# IOPROTO96.net
KiCad netlist of a schematic drawn in EAGLE
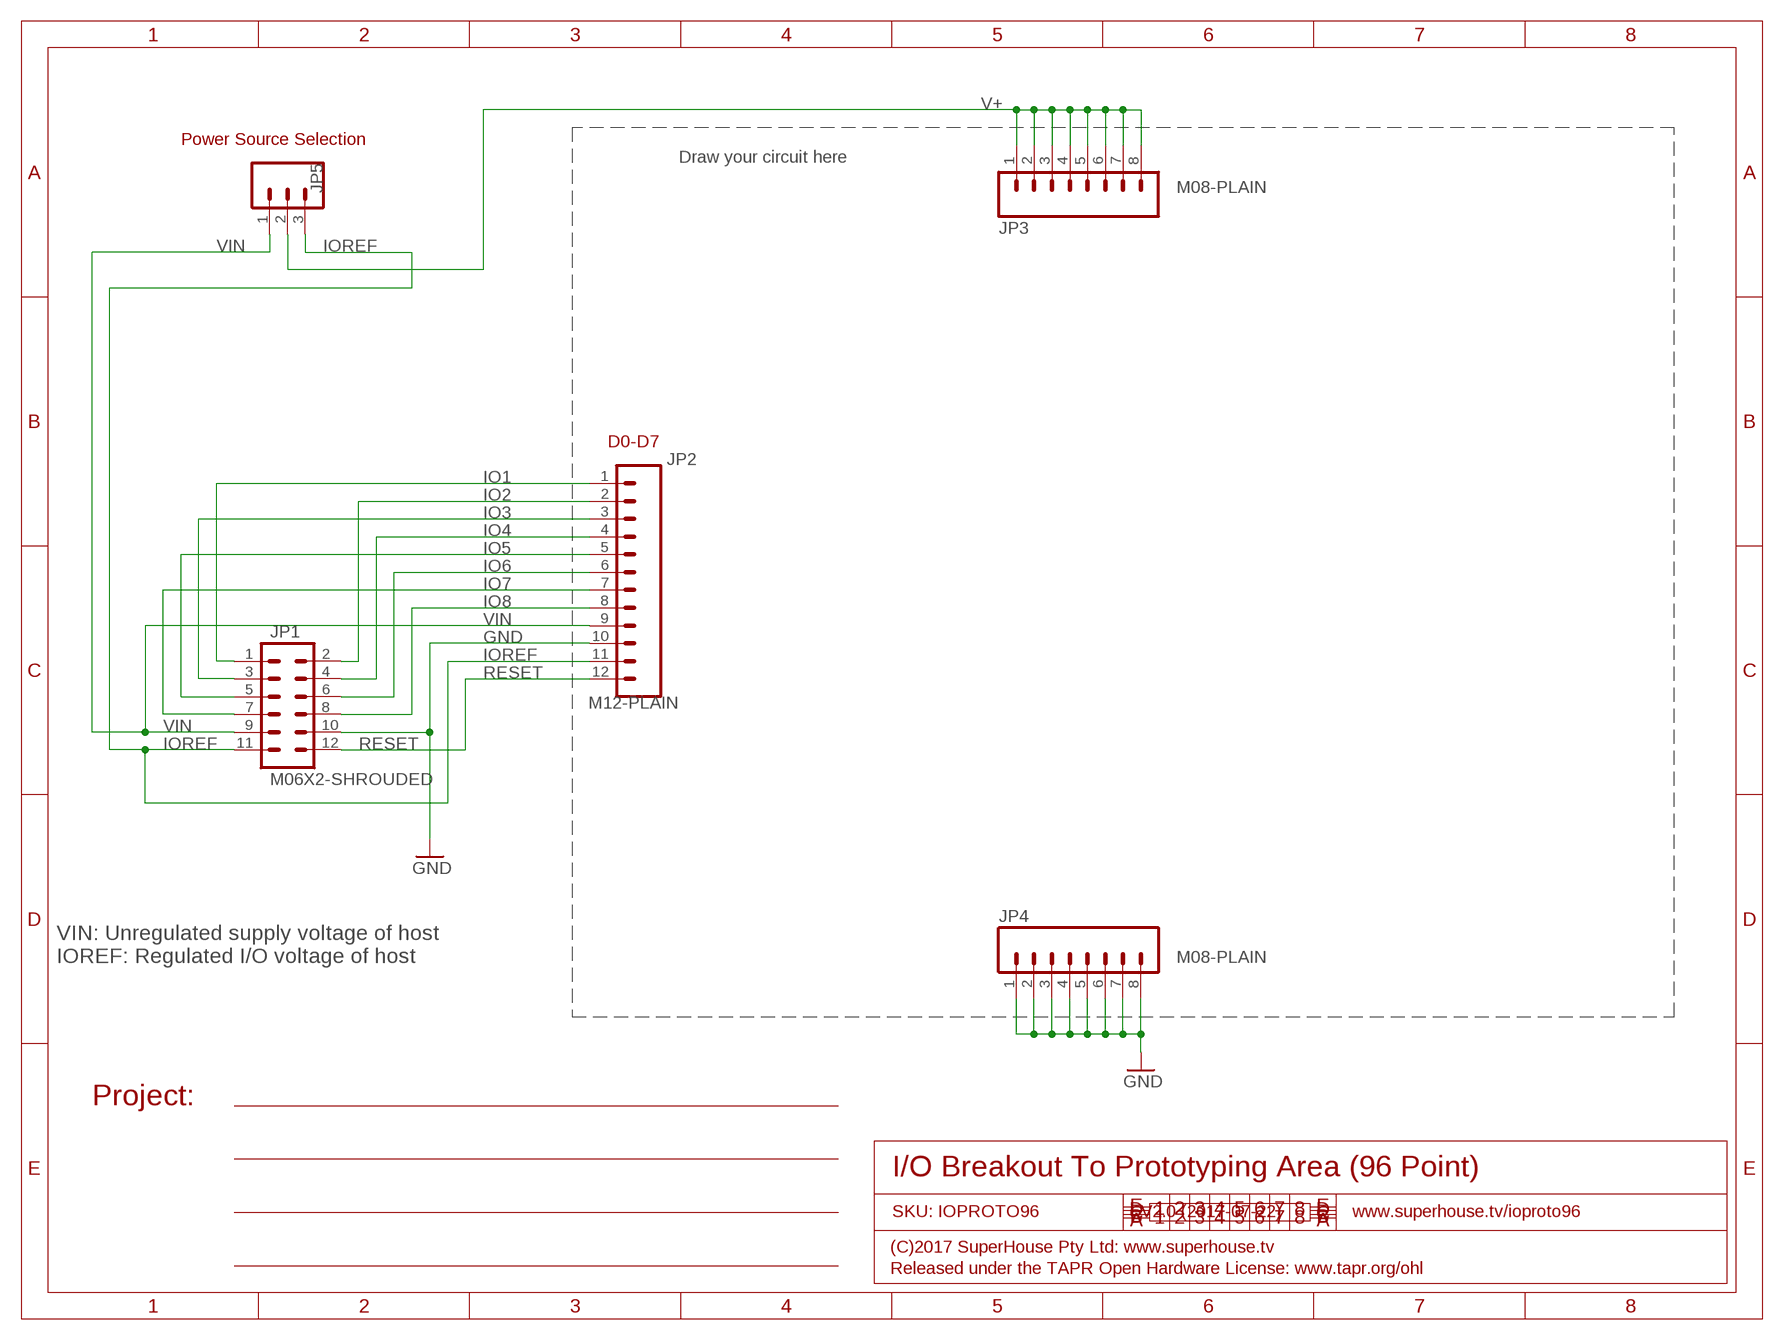
[diagram p0: schematic, sheet 1]

(export (version "E")
  (design (tool "Eeschema 10.0.6"))
  (components
    (comp (ref "JP1")
      (value "M06X2-SHROUDED")
      (footprint "eagle-import:2X6-SHROUDED")
      (libsource (lib "eagle-import") (part "M06X2-SHROUDED"))
    )
    (comp (ref "JP2")
      (value "M12-PLAIN")
      (footprint "eagle-import:1X12")
      (libsource (lib "eagle-import") (part "M12-PLAIN"))
    )
    (comp (ref "JP3")
      (value "M08-PLAIN")
      (footprint "eagle-import:1X08")
      (libsource (lib "eagle-import") (part "M08-PLAIN"))
    )
    (comp (ref "JP4")
      (value "M08-PLAIN")
      (footprint "eagle-import:1X08")
      (libsource (lib "eagle-import") (part "M08-PLAIN"))
    )
    (comp (ref "JP5")
      (value "M03-PIN")
      (footprint "eagle-import:1X03-P")
      (libsource (lib "eagle-import") (part "M03-PIN"))
    )
  )
  (nets
    (net (code "1") (name "/IO1") (class "Default")
      (node (ref "JP1") (pin "1") (pinfunction "1_1") (pintype "passive"))
      (node (ref "JP2") (pin "1") (pinfunction "1_1") (pintype "passive"))
    )
    (net (code "2") (name "/IO2") (class "Default")
      (node (ref "JP1") (pin "2") (pinfunction "2_2") (pintype "passive"))
      (node (ref "JP2") (pin "2") (pinfunction "2_2") (pintype "passive"))
    )
    (net (code "3") (name "/IO3") (class "Default")
      (node (ref "JP1") (pin "3") (pinfunction "3_3") (pintype "passive"))
      (node (ref "JP2") (pin "3") (pinfunction "3_3") (pintype "passive"))
    )
    (net (code "4") (name "/IO4") (class "Default")
      (node (ref "JP1") (pin "4") (pinfunction "4_4") (pintype "passive"))
      (node (ref "JP2") (pin "4") (pinfunction "4_4") (pintype "passive"))
    )
    (net (code "5") (name "/IO5") (class "Default")
      (node (ref "JP1") (pin "5") (pinfunction "5_5") (pintype "passive"))
      (node (ref "JP2") (pin "5") (pinfunction "5_5") (pintype "passive"))
    )
    (net (code "6") (name "/IO6") (class "Default")
      (node (ref "JP1") (pin "6") (pinfunction "6_6") (pintype "passive"))
      (node (ref "JP2") (pin "6") (pinfunction "6_6") (pintype "passive"))
    )
    (net (code "7") (name "/IO7") (class "Default")
      (node (ref "JP1") (pin "7") (pinfunction "7_7") (pintype "passive"))
      (node (ref "JP2") (pin "7") (pinfunction "7_7") (pintype "passive"))
    )
    (net (code "8") (name "/IO8") (class "Default")
      (node (ref "JP1") (pin "8") (pinfunction "8_8") (pintype "passive"))
      (node (ref "JP2") (pin "8") (pinfunction "8_8") (pintype "passive"))
    )
    (net (code "9") (name "/IOREF") (class "Default")
      (node (ref "JP1") (pin "11") (pinfunction "11_11") (pintype "passive"))
      (node (ref "JP2") (pin "11") (pinfunction "11_11") (pintype "passive"))
      (node (ref "JP5") (pin "3") (pinfunction "3_3") (pintype "passive"))
    )
    (net (code "10") (name "/RESET") (class "Default")
      (node (ref "JP1") (pin "12") (pinfunction "12_12") (pintype "passive"))
      (node (ref "JP2") (pin "12") (pinfunction "12_12") (pintype "passive"))
    )
    (net (code "11") (name "/V+") (class "Default")
      (node (ref "JP3") (pin "1") (pinfunction "1_1") (pintype "passive"))
      (node (ref "JP3") (pin "2") (pinfunction "2_2") (pintype "passive"))
      (node (ref "JP3") (pin "3") (pinfunction "3_3") (pintype "passive"))
      (node (ref "JP3") (pin "4") (pinfunction "4_4") (pintype "passive"))
      (node (ref "JP3") (pin "5") (pinfunction "5_5") (pintype "passive"))
      (node (ref "JP3") (pin "6") (pinfunction "6_6") (pintype "passive"))
      (node (ref "JP3") (pin "7") (pinfunction "7_7") (pintype "passive"))
      (node (ref "JP3") (pin "8") (pinfunction "8_8") (pintype "passive"))
      (node (ref "JP5") (pin "2") (pinfunction "2_2") (pintype "passive"))
    )
    (net (code "12") (name "/VIN") (class "Default")
      (node (ref "JP1") (pin "9") (pinfunction "9_9") (pintype "passive"))
      (node (ref "JP2") (pin "9") (pinfunction "9_9") (pintype "passive"))
      (node (ref "JP5") (pin "1") (pinfunction "1_1") (pintype "passive"))
    )
    (net (code "13") (name "GND") (class "Default")
      (node (ref "JP1") (pin "10") (pinfunction "10_10") (pintype "passive"))
      (node (ref "JP2") (pin "10") (pinfunction "10_10") (pintype "passive"))
      (node (ref "JP4") (pin "1") (pinfunction "1_1") (pintype "passive"))
      (node (ref "JP4") (pin "2") (pinfunction "2_2") (pintype "passive"))
      (node (ref "JP4") (pin "3") (pinfunction "3_3") (pintype "passive"))
      (node (ref "JP4") (pin "4") (pinfunction "4_4") (pintype "passive"))
      (node (ref "JP4") (pin "5") (pinfunction "5_5") (pintype "passive"))
      (node (ref "JP4") (pin "6") (pinfunction "6_6") (pintype "passive"))
      (node (ref "JP4") (pin "7") (pinfunction "7_7") (pintype "passive"))
      (node (ref "JP4") (pin "8") (pinfunction "8_8") (pintype "passive"))
    )
  )
)
